# working.net
KiCad netlist of a schematic drawn in EAGLE
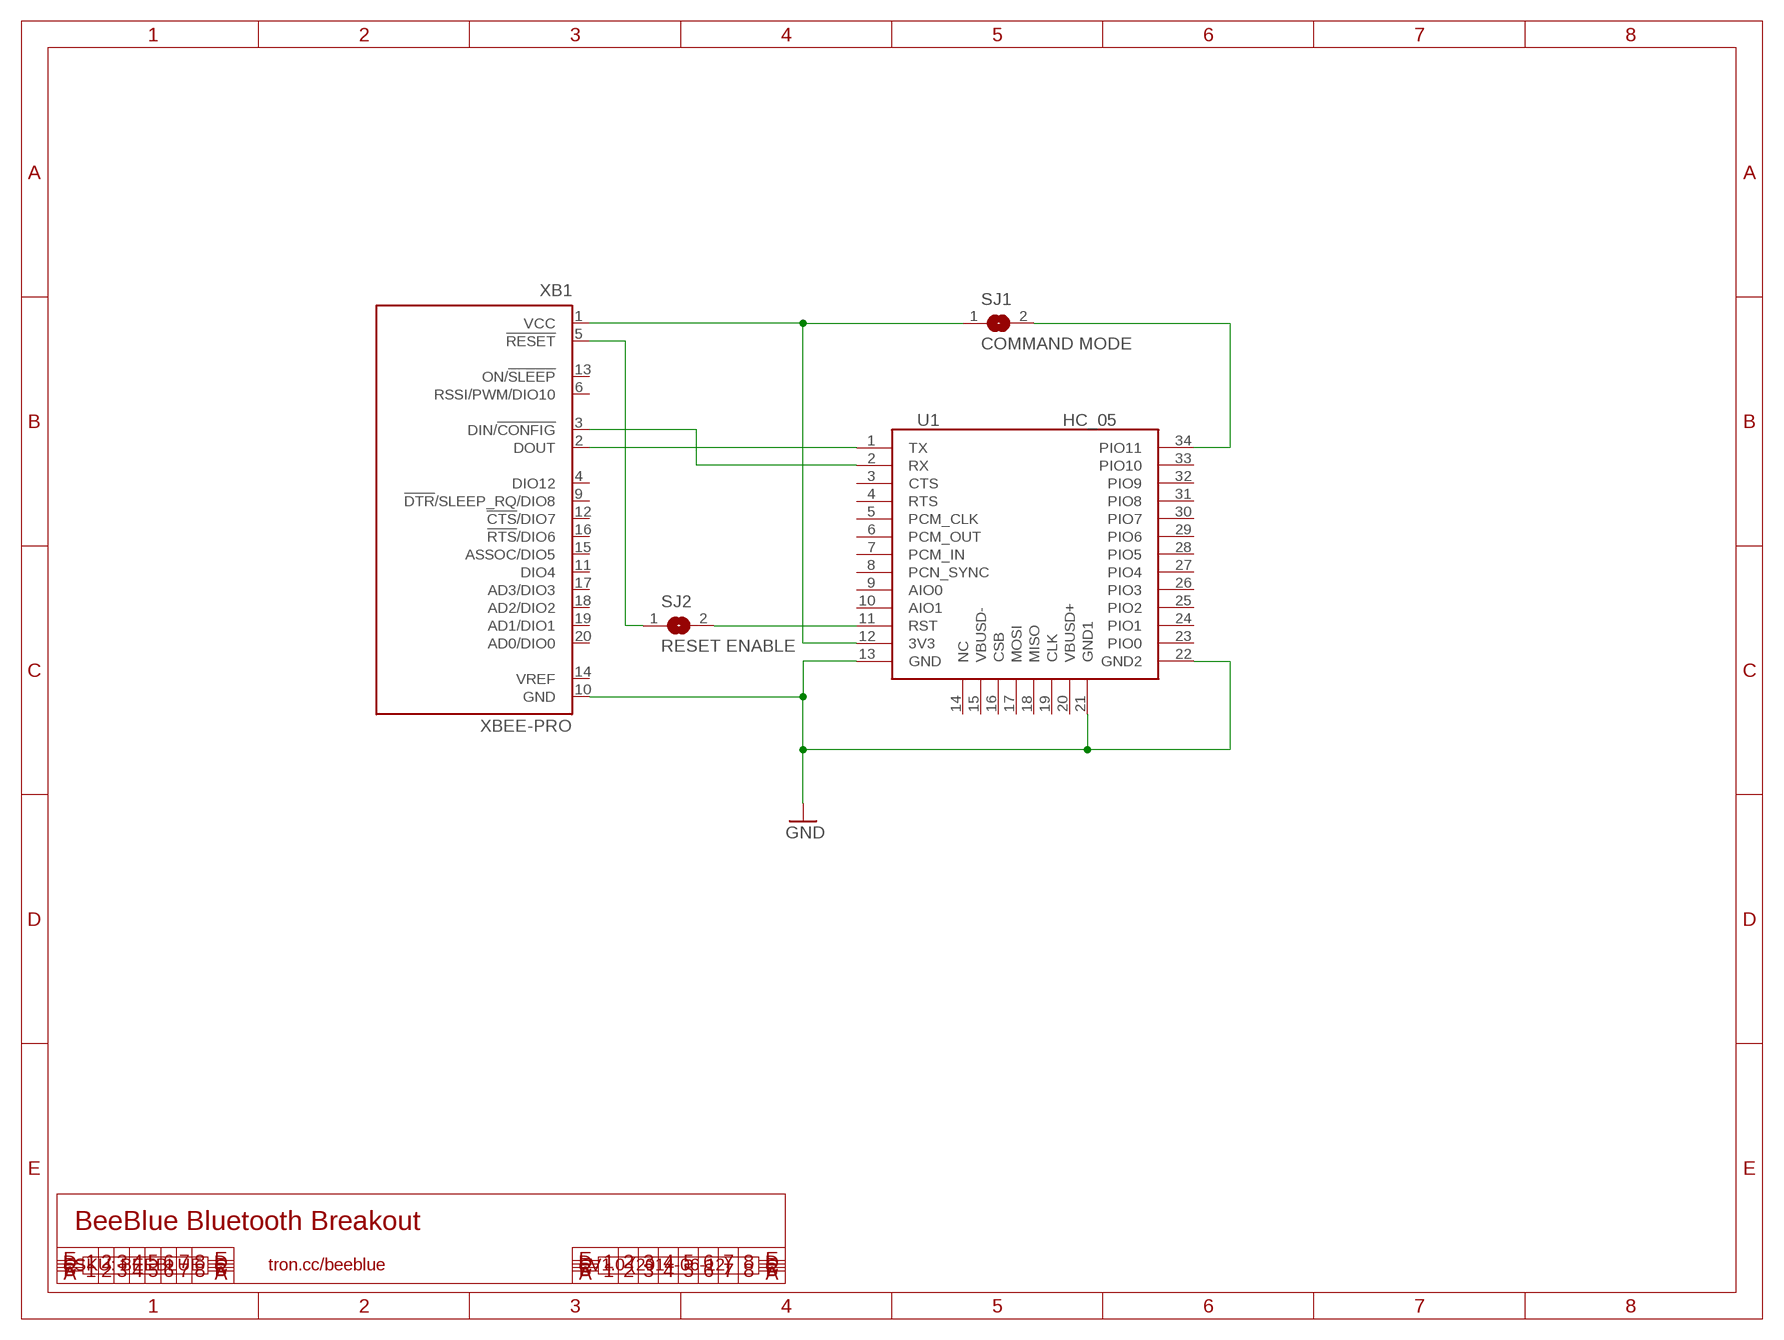
[diagram p0: schematic, sheet 1]

(export (version "E")
  (design (tool "Eeschema 10.0.6"))
  (components
    (comp (ref "SJ1")
      (value "COMMAND MODE")
      (footprint "eagle-import:SJ")
      (libsource (lib "eagle-import") (part "SJN"))
    )
    (comp (ref "SJ2")
      (value "RESET ENABLE")
      (footprint "eagle-import:SJ")
      (libsource (lib "eagle-import") (part "SJN"))
    )
    (comp (ref "U1")
      (value "HC_05")
      (footprint "eagle-import:BLUETOOTH_SMD")
      (libsource (lib "eagle-import") (part "HC_05"))
    )
    (comp (ref "XB1")
      (value "XBEE-PRO")
      (footprint "eagle-import:XBEE-PRO")
      (fields (field (name "MPN") "XBP24-AWI-001"))
      (libsource (lib "eagle-import") (part "XBEE-PRO"))
    )
  )
  (nets
    (net (code "1") (name "GND") (class "Default")
      (node (ref "U1") (pin "13") (pinfunction "GND_13") (pintype "bidirectional"))
      (node (ref "U1") (pin "21") (pinfunction "GND1_21") (pintype "bidirectional"))
      (node (ref "U1") (pin "22") (pinfunction "GND2_22") (pintype "bidirectional"))
      (node (ref "XB1") (pin "10") (pinfunction "GND_10") (pintype "power_in"))
    )
    (net (code "2") (name "Net-(U1-3V3)") (class "Default")
      (node (ref "SJ1") (pin "1") (pinfunction "1_1") (pintype "passive"))
      (node (ref "U1") (pin "12") (pinfunction "3V3_12") (pintype "bidirectional"))
      (node (ref "XB1") (pin "1") (pinfunction "VCC_1") (pintype "power_in"))
    )
    (net (code "3") (name "Net-(U1-PIO11)") (class "Default")
      (node (ref "SJ1") (pin "2") (pinfunction "2_2") (pintype "passive"))
      (node (ref "U1") (pin "34") (pinfunction "PIO11_34") (pintype "bidirectional"))
    )
    (net (code "4") (name "Net-(U1-RST)") (class "Default")
      (node (ref "SJ2") (pin "2") (pinfunction "2_2") (pintype "passive"))
      (node (ref "U1") (pin "11") (pinfunction "RST_11") (pintype "bidirectional"))
    )
    (net (code "5") (name "Net-(U1-RX)") (class "Default")
      (node (ref "U1") (pin "2") (pinfunction "RX_2") (pintype "bidirectional"))
      (node (ref "XB1") (pin "3") (pinfunction "DIN/~{CONFIG}_3") (pintype "input"))
    )
    (net (code "6") (name "Net-(U1-TX)") (class "Default")
      (node (ref "U1") (pin "1") (pinfunction "TX_1") (pintype "bidirectional"))
      (node (ref "XB1") (pin "2") (pinfunction "DOUT_2") (pintype "output"))
    )
    (net (code "7") (name "Net-(XB1-~{RESET})") (class "Default")
      (node (ref "SJ2") (pin "1") (pinfunction "1_1") (pintype "passive"))
      (node (ref "XB1") (pin "5") (pinfunction "~{RESET}_5") (pintype "input"))
    )
    (net (code "8") (name "unconnected-(U1-AIO0-Pad9)") (class "Default")
      (node (ref "U1") (pin "9") (pinfunction "AIO0_9") (pintype "bidirectional"))
    )
    (net (code "9") (name "unconnected-(U1-AIO1-Pad10)") (class "Default")
      (node (ref "U1") (pin "10") (pinfunction "AIO1_10") (pintype "bidirectional"))
    )
    (net (code "10") (name "unconnected-(U1-CLK-Pad19)") (class "Default")
      (node (ref "U1") (pin "19") (pinfunction "CLK_19") (pintype "bidirectional"))
    )
    (net (code "11") (name "unconnected-(U1-CSB-Pad16)") (class "Default")
      (node (ref "U1") (pin "16") (pinfunction "CSB_16") (pintype "bidirectional"))
    )
    (net (code "12") (name "unconnected-(U1-CTS-Pad3)") (class "Default")
      (node (ref "U1") (pin "3") (pinfunction "CTS_3") (pintype "bidirectional"))
    )
    (net (code "13") (name "unconnected-(U1-MISO-Pad18)") (class "Default")
      (node (ref "U1") (pin "18") (pinfunction "MISO_18") (pintype "bidirectional"))
    )
    (net (code "14") (name "unconnected-(U1-MOSI-Pad17)") (class "Default")
      (node (ref "U1") (pin "17") (pinfunction "MOSI_17") (pintype "bidirectional"))
    )
    (net (code "15") (name "unconnected-(U1-NC-Pad14)") (class "Default")
      (node (ref "U1") (pin "14") (pinfunction "NC_14") (pintype "bidirectional"))
    )
    (net (code "16") (name "unconnected-(U1-PCM_CLK-Pad5)") (class "Default")
      (node (ref "U1") (pin "5") (pinfunction "PCM_CLK_5") (pintype "bidirectional"))
    )
    (net (code "17") (name "unconnected-(U1-PCM_IN-Pad7)") (class "Default")
      (node (ref "U1") (pin "7") (pinfunction "PCM_IN_7") (pintype "bidirectional"))
    )
    (net (code "18") (name "unconnected-(U1-PCM_OUT-Pad6)") (class "Default")
      (node (ref "U1") (pin "6") (pinfunction "PCM_OUT_6") (pintype "bidirectional"))
    )
    (net (code "19") (name "unconnected-(U1-PCN_SYNC-Pad8)") (class "Default")
      (node (ref "U1") (pin "8") (pinfunction "PCN_SYNC_8") (pintype "bidirectional"))
    )
    (net (code "20") (name "unconnected-(U1-PIO0-Pad23)") (class "Default")
      (node (ref "U1") (pin "23") (pinfunction "PIO0_23") (pintype "bidirectional"))
    )
    (net (code "21") (name "unconnected-(U1-PIO1-Pad24)") (class "Default")
      (node (ref "U1") (pin "24") (pinfunction "PIO1_24") (pintype "bidirectional"))
    )
    (net (code "22") (name "unconnected-(U1-PIO2-Pad25)") (class "Default")
      (node (ref "U1") (pin "25") (pinfunction "PIO2_25") (pintype "bidirectional"))
    )
    (net (code "23") (name "unconnected-(U1-PIO3-Pad26)") (class "Default")
      (node (ref "U1") (pin "26") (pinfunction "PIO3_26") (pintype "bidirectional"))
    )
    (net (code "24") (name "unconnected-(U1-PIO4-Pad27)") (class "Default")
      (node (ref "U1") (pin "27") (pinfunction "PIO4_27") (pintype "bidirectional"))
    )
    (net (code "25") (name "unconnected-(U1-PIO5-Pad28)") (class "Default")
      (node (ref "U1") (pin "28") (pinfunction "PIO5_28") (pintype "bidirectional"))
    )
    (net (code "26") (name "unconnected-(U1-PIO6-Pad29)") (class "Default")
      (node (ref "U1") (pin "29") (pinfunction "PIO6_29") (pintype "bidirectional"))
    )
    (net (code "27") (name "unconnected-(U1-PIO7-Pad30)") (class "Default")
      (node (ref "U1") (pin "30") (pinfunction "PIO7_30") (pintype "bidirectional"))
    )
    (net (code "28") (name "unconnected-(U1-PIO8-Pad31)") (class "Default")
      (node (ref "U1") (pin "31") (pinfunction "PIO8_31") (pintype "bidirectional"))
    )
    (net (code "29") (name "unconnected-(U1-PIO9-Pad32)") (class "Default")
      (node (ref "U1") (pin "32") (pinfunction "PIO9_32") (pintype "bidirectional"))
    )
    (net (code "30") (name "unconnected-(U1-PIO10-Pad33)") (class "Default")
      (node (ref "U1") (pin "33") (pinfunction "PIO10_33") (pintype "bidirectional"))
    )
    (net (code "31") (name "unconnected-(U1-RTS-Pad4)") (class "Default")
      (node (ref "U1") (pin "4") (pinfunction "RTS_4") (pintype "bidirectional"))
    )
    (net (code "32") (name "unconnected-(U1-VBUSD+-Pad20)") (class "Default")
      (node (ref "U1") (pin "20") (pinfunction "VBUSD+_20") (pintype "bidirectional"))
    )
    (net (code "33") (name "unconnected-(U1-VBUSD--Pad15)") (class "Default")
      (node (ref "U1") (pin "15") (pinfunction "VBUSD-_15") (pintype "bidirectional"))
    )
    (net (code "34") (name "unconnected-(XB1-AD0{slash}DIO0-Pad20)") (class "Default")
      (node (ref "XB1") (pin "20") (pinfunction "AD0/DIO0_20") (pintype "bidirectional"))
    )
    (net (code "35") (name "unconnected-(XB1-AD1{slash}DIO1-Pad19)") (class "Default")
      (node (ref "XB1") (pin "19") (pinfunction "AD1/DIO1_19") (pintype "bidirectional"))
    )
    (net (code "36") (name "unconnected-(XB1-AD2{slash}DIO2-Pad18)") (class "Default")
      (node (ref "XB1") (pin "18") (pinfunction "AD2/DIO2_18") (pintype "bidirectional"))
    )
    (net (code "37") (name "unconnected-(XB1-AD3{slash}DIO3-Pad17)") (class "Default")
      (node (ref "XB1") (pin "17") (pinfunction "AD3/DIO3_17") (pintype "bidirectional"))
    )
    (net (code "38") (name "unconnected-(XB1-ASSOC{slash}DIO5-Pad15)") (class "Default")
      (node (ref "XB1") (pin "15") (pinfunction "ASSOC/DIO5_15") (pintype "bidirectional"))
    )
    (net (code "39") (name "unconnected-(XB1-DIO4-Pad11)") (class "Default")
      (node (ref "XB1") (pin "11") (pinfunction "DIO4_11") (pintype "bidirectional"))
    )
    (net (code "40") (name "unconnected-(XB1-DIO12-Pad4)") (class "Default")
      (node (ref "XB1") (pin "4") (pinfunction "DIO12_4") (pintype "bidirectional"))
    )
    (net (code "41") (name "unconnected-(XB1-ON{slash}~{SLEEP}-Pad13)") (class "Default")
      (node (ref "XB1") (pin "13") (pinfunction "ON/~{SLEEP}_13") (pintype "output"))
    )
    (net (code "42") (name "unconnected-(XB1-RSSI{slash}PWM{slash}DIO10-Pad6)") (class "Default")
      (node (ref "XB1") (pin "6") (pinfunction "RSSI/PWM/DIO10_6") (pintype "output"))
    )
    (net (code "43") (name "unconnected-(XB1-VREF-Pad14)") (class "Default")
      (node (ref "XB1") (pin "14") (pinfunction "VREF_14") (pintype "input"))
    )
    (net (code "44") (name "unconnected-(XB1-~{CTS}{slash}DIO7-Pad12)") (class "Default")
      (node (ref "XB1") (pin "12") (pinfunction "~{CTS}/DIO7_12") (pintype "bidirectional"))
    )
    (net (code "45") (name "unconnected-(XB1-~{DTR}{slash}SLEEP_RQ{slash}DIO8-Pad9)") (class "Default")
      (node (ref "XB1") (pin "9") (pinfunction "~{DTR}/SLEEP_RQ/DIO8_9") (pintype "bidirectional"))
    )
    (net (code "46") (name "unconnected-(XB1-~{RTS}{slash}DIO6-Pad16)") (class "Default")
      (node (ref "XB1") (pin "16") (pinfunction "~{RTS}/DIO6_16") (pintype "bidirectional"))
    )
  )
)
